# Sheet1.net
KiCad netlist of a schematic drawn in Altium Designer
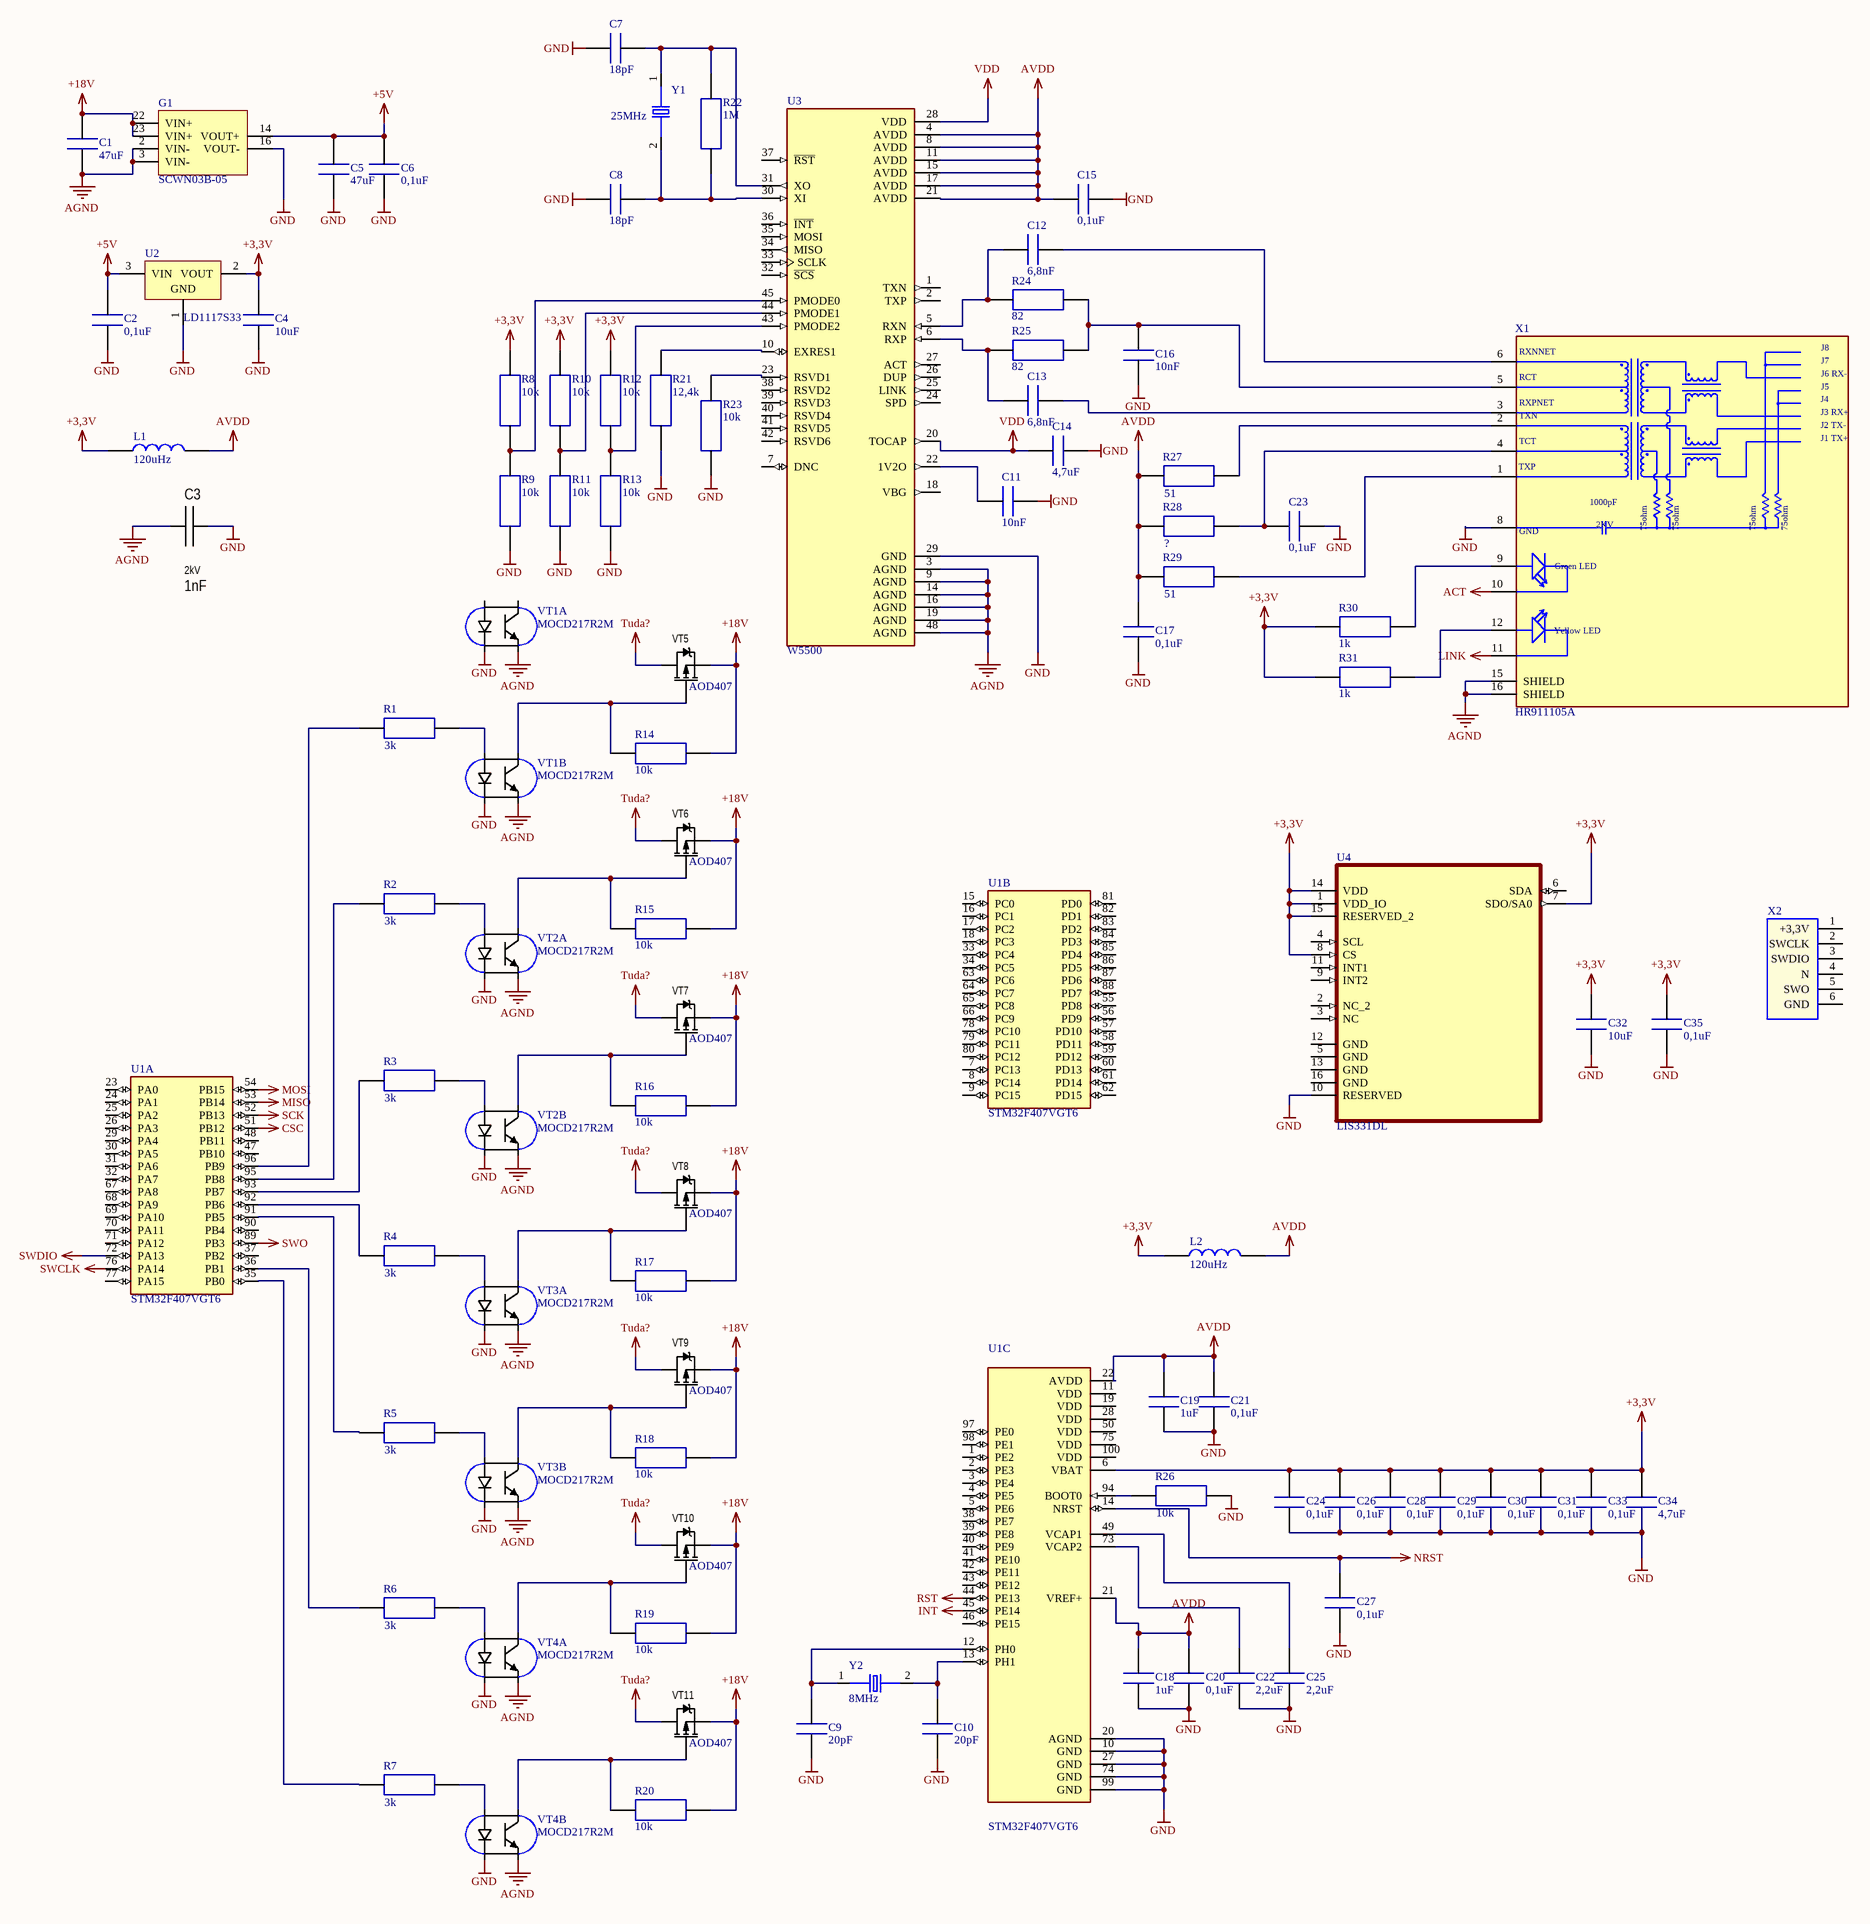
[diagram p0: Sheet1.SchDoc]

(export (version "E")
  (design (tool "Eeschema 10.0.6"))
  (components
    (comp (ref "C1") (value "47uF") (footprint "0603") (libsource (lib "Schlib1") (part "Cap")))
    (comp (ref "C2") (value "0,1uF") (footprint "0603") (libsource (lib "Schlib1") (part "Cap")))
    (comp (ref "C3")
      (value "1nF")
      (footprint "CAP: 1206")
      (fields
        (field (name "MANUFACTURER") "Yageo")
        (field (name "PARTNUMBER") "CC1206KRX7R9BB104")
        (field (name "VALUEMANUFACTURERPARTNUMBER") "Ceramic capacitor, 1nF, X7R, ±10%, 2kV, 1206, -55...+125°C")
        (field (name "VOLTAGE") "2kV")
      )
      (libsource (lib "capacitor") (part "Ceramic_1206"))
    )
    (comp (ref "C4") (value "10uF") (footprint "0603") (libsource (lib "Schlib1") (part "Cap")))
    (comp (ref "C5") (value "47uF") (footprint "0603") (libsource (lib "Schlib1") (part "Cap")))
    (comp (ref "C6") (value "0,1uF") (footprint "0603") (libsource (lib "Schlib1") (part "Cap")))
    (comp (ref "C7") (value "18pF") (footprint "0603") (libsource (lib "Schlib1") (part "Cap")))
    (comp (ref "C8") (value "18pF") (footprint "0603") (libsource (lib "Schlib1") (part "Cap")))
    (comp (ref "C9") (value "20pF") (footprint "0603") (libsource (lib "Schlib1") (part "Cap")))
    (comp (ref "C10") (value "20pF") (footprint "0603") (libsource (lib "Schlib1") (part "Cap")))
    (comp (ref "C11") (value "10nF") (footprint "0603") (libsource (lib "Schlib1") (part "Cap")))
    (comp (ref "C12") (value "6,8nF") (footprint "0603") (libsource (lib "Schlib1") (part "Cap")))
    (comp (ref "C13") (value "6,8nF") (footprint "0603") (libsource (lib "Schlib1") (part "Cap")))
    (comp (ref "C14") (value "4,7uF") (footprint "0603") (libsource (lib "Schlib1") (part "Cap")))
    (comp (ref "C15") (value "0,1uF") (footprint "0603") (libsource (lib "Schlib1") (part "Cap")))
    (comp (ref "C16") (value "10nF") (footprint "0603") (libsource (lib "Schlib1") (part "Cap")))
    (comp (ref "C17") (value "0,1uF") (footprint "0603") (libsource (lib "Schlib1") (part "Cap")))
    (comp (ref "C18") (value "1uF") (footprint "0603") (libsource (lib "Schlib1") (part "Cap")))
    (comp (ref "C19") (value "1uF") (footprint "0603") (libsource (lib "Schlib1") (part "Cap")))
    (comp (ref "C20") (value "0,1uF") (footprint "0603") (libsource (lib "Schlib1") (part "Cap")))
    (comp (ref "C21") (value "0,1uF") (footprint "0603") (libsource (lib "Schlib1") (part "Cap")))
    (comp (ref "C22") (value "2,2uF") (footprint "0603") (libsource (lib "Schlib1") (part "Cap")))
    (comp (ref "C23") (value "0,1uF") (footprint "0603") (libsource (lib "Schlib1") (part "Cap")))
    (comp (ref "C24") (value "0,1uF") (footprint "0603") (libsource (lib "Schlib1") (part "Cap")))
    (comp (ref "C25") (value "2,2uF") (footprint "0603") (libsource (lib "Schlib1") (part "Cap")))
    (comp (ref "C26") (value "0,1uF") (footprint "0603") (libsource (lib "Schlib1") (part "Cap")))
    (comp (ref "C27") (value "0,1uF") (footprint "0603") (libsource (lib "Schlib1") (part "Cap")))
    (comp (ref "C28") (value "0,1uF") (footprint "0603") (libsource (lib "Schlib1") (part "Cap")))
    (comp (ref "C29") (value "0,1uF") (footprint "0603") (libsource (lib "Schlib1") (part "Cap")))
    (comp (ref "C30") (value "0,1uF") (footprint "0603") (libsource (lib "Schlib1") (part "Cap")))
    (comp (ref "C31") (value "0,1uF") (footprint "0603") (libsource (lib "Schlib1") (part "Cap")))
    (comp (ref "C32") (value "10uF") (footprint "0603") (libsource (lib "Schlib1") (part "Cap")))
    (comp (ref "C33") (value "0,1uF") (footprint "0603") (libsource (lib "Schlib1") (part "Cap")))
    (comp (ref "C34") (value "4,7uF") (footprint "0603") (libsource (lib "Schlib1") (part "Cap")))
    (comp (ref "C35") (value "0,1uF") (footprint "0603") (libsource (lib "Schlib1") (part "Cap")))
    (comp (ref "G1")
      (value "SCWN03B-05")
      (footprint "DIP")
      (description "DC-DC Regulated Converter DIP")
      (libsource (lib "Schlib1") (part "SCWN03B-05"))
    )
    (comp (ref "L1") (value "120uHz") (footprint "0603") (libsource (lib "Schlib1") (part "Ind")))
    (comp (ref "L2") (value "120uHz") (footprint "0603") (libsource (lib "Schlib1") (part "Ind")))
    (comp (ref "R1") (value "3k") (footprint "0603") (libsource (lib "Schlib1") (part "Rez")))
    (comp (ref "R2") (value "3k") (footprint "0603") (libsource (lib "Schlib1") (part "Rez")))
    (comp (ref "R3") (value "3k") (footprint "0603") (libsource (lib "Schlib1") (part "Rez")))
    (comp (ref "R4") (value "3k") (footprint "0603") (libsource (lib "Schlib1") (part "Rez")))
    (comp (ref "R5") (value "3k") (footprint "0603") (libsource (lib "Schlib1") (part "Rez")))
    (comp (ref "R6") (value "3k") (footprint "0603") (libsource (lib "Schlib1") (part "Rez")))
    (comp (ref "R7") (value "3k") (footprint "0603") (libsource (lib "Schlib1") (part "Rez")))
    (comp (ref "R8") (value "10k") (footprint "0603") (libsource (lib "Schlib1") (part "Rez")))
    (comp (ref "R9") (value "10k") (footprint "0603") (libsource (lib "Schlib1") (part "Rez")))
    (comp (ref "R10") (value "10k") (footprint "0603") (libsource (lib "Schlib1") (part "Rez")))
    (comp (ref "R11") (value "10k") (footprint "0603") (libsource (lib "Schlib1") (part "Rez")))
    (comp (ref "R12") (value "10k") (footprint "0603") (libsource (lib "Schlib1") (part "Rez")))
    (comp (ref "R13") (value "10k") (footprint "0603") (libsource (lib "Schlib1") (part "Rez")))
    (comp (ref "R14") (value "10k") (footprint "0603") (libsource (lib "Schlib1") (part "Rez")))
    (comp (ref "R15") (value "10k") (footprint "0603") (libsource (lib "Schlib1") (part "Rez")))
    (comp (ref "R16") (value "10k") (footprint "0603") (libsource (lib "Schlib1") (part "Rez")))
    (comp (ref "R17") (value "10k") (footprint "0603") (libsource (lib "Schlib1") (part "Rez")))
    (comp (ref "R18") (value "10k") (footprint "0603") (libsource (lib "Schlib1") (part "Rez")))
    (comp (ref "R19") (value "10k") (footprint "0603") (libsource (lib "Schlib1") (part "Rez")))
    (comp (ref "R20") (value "10k") (footprint "0603") (libsource (lib "Schlib1") (part "Rez")))
    (comp (ref "R21") (value "12,4k") (footprint "0603") (libsource (lib "Schlib1") (part "Rez")))
    (comp (ref "R22") (value "1M") (footprint "0603") (libsource (lib "Schlib1") (part "Rez")))
    (comp (ref "R23") (value "10k") (footprint "0603") (libsource (lib "Schlib1") (part "Rez")))
    (comp (ref "R24") (value "82") (footprint "0603") (libsource (lib "Schlib1") (part "Rez")))
    (comp (ref "R25") (value "82") (footprint "0603") (libsource (lib "Schlib1") (part "Rez")))
    (comp (ref "R26") (value "10k") (footprint "0603") (libsource (lib "Schlib1") (part "Rez")))
    (comp (ref "R27") (value "51") (footprint "0603") (libsource (lib "Schlib1") (part "Rez")))
    (comp (ref "R28") (value "?") (footprint "0603") (libsource (lib "Schlib1") (part "Rez")))
    (comp (ref "R29") (value "51") (footprint "0603") (libsource (lib "Schlib1") (part "Rez")))
    (comp (ref "R30") (value "1k") (footprint "0603") (libsource (lib "Schlib1") (part "Rez")))
    (comp (ref "R31") (value "1k") (footprint "0603") (libsource (lib "Schlib1") (part "Rez")))
    (comp (ref "U1")
      (value "STM32F407VGT6")
      (footprint "QFP50P1600X1600X160-100N")
      (description "ARMÂ® CortexÂ®-M4 STM32F4 Microcontroller IC 32-Bit 168MHz 1MB _1M x 8_ FLASH 100-LQFP _14x14_")
      (fields (field (name "MF") "STMicroelectronics"))
      (libsource (lib "STM32F407VGT6") (part "STM32F407VGT6"))
    )
    (comp (ref "U2")
      (value "LD1117S33")
      (footprint "SOT-223L")
      (description "Adjustable and fixed low drop positive voltage regulator, SOT-223")
      (libsource (lib "Schlib1") (part "LD1117S33"))
    )
    (comp (ref "U3")
      (value "W5500")
      (footprint "QFP50P900X900X160-48N")
      (description "Socket Contact Silver 17-20 AWG Crimp Power")
      (fields (field (name "MF") "WIZnet"))
      (libsource (lib "W5500") (part "W5500"))
    )
    (comp (ref "U4")
      (value "LIS331DL")
      (footprint "LGA16R50P3X5_300X300X100")
      (description "ÐÐºÑÐµÐ»ÐµÑ€Ð¾Ð¼ÐµÑ‚Ñ€ Ð¿Ð¾ Ð¾ÑÑÐ¼ X, Y, Z Â± 2g, 4g, 8g 25 Ð“Ñ† ~ 500 Ð“Ñ† 16-LGA (3x3)")
      (fields (field (name "MF") "STMicroelectronics"))
      (libsource (lib "LIS331DL") (part "LIS331DL"))
    )
    (comp (ref "VT1") (value "MOCD217R2M") (footprint "SO-8") (libsource (lib "Schlib1") (part "Opto")))
    (comp (ref "VT2") (value "MOCD217R2M") (footprint "SO-8") (libsource (lib "Schlib1") (part "Opto")))
    (comp (ref "VT3") (value "MOCD217R2M") (footprint "SO-8") (libsource (lib "Schlib1") (part "Opto")))
    (comp (ref "VT4") (value "MOCD217R2M") (footprint "SO-8") (libsource (lib "Schlib1") (part "Opto")))
    (comp (ref "VT5")
      (value "AOD407")
      (footprint "SOT23")
      (fields
        (field (name "MANUFACTURER") "Infineon Technologies")
        (field (name "VALUEMANUFACTURERPARTNUMBER") "MOSFET P-channel transistor, 20V, 2.6A, 2.9nC, 2.5W, 135mOhm, 220pF, SOT-23, -55...+150°C")
        (field (name "PARTNUMBER") "IRLML2246TRPBF")
      )
      (libsource (lib "transistor") (part "MOSFET_P_123"))
    )
    (comp (ref "VT6")
      (value "AOD407")
      (footprint "SOT23")
      (fields
        (field (name "MANUFACTURER") "Infineon Technologies")
        (field (name "VALUEMANUFACTURERPARTNUMBER") "MOSFET P-channel transistor, 20V, 2.6A, 2.9nC, 2.5W, 135mOhm, 220pF, SOT-23, -55...+150°C")
        (field (name "PARTNUMBER") "IRLML2246TRPBF")
      )
      (libsource (lib "transistor") (part "MOSFET_P_123"))
    )
    (comp (ref "VT7")
      (value "AOD407")
      (footprint "SOT23")
      (fields
        (field (name "MANUFACTURER") "Infineon Technologies")
        (field (name "VALUEMANUFACTURERPARTNUMBER") "MOSFET P-channel transistor, 20V, 2.6A, 2.9nC, 2.5W, 135mOhm, 220pF, SOT-23, -55...+150°C")
        (field (name "PARTNUMBER") "IRLML2246TRPBF")
      )
      (libsource (lib "transistor") (part "MOSFET_P_123"))
    )
    (comp (ref "VT8")
      (value "AOD407")
      (footprint "SOT23")
      (fields
        (field (name "MANUFACTURER") "Infineon Technologies")
        (field (name "VALUEMANUFACTURERPARTNUMBER") "MOSFET P-channel transistor, 20V, 2.6A, 2.9nC, 2.5W, 135mOhm, 220pF, SOT-23, -55...+150°C")
        (field (name "PARTNUMBER") "IRLML2246TRPBF")
      )
      (libsource (lib "transistor") (part "MOSFET_P_123"))
    )
    (comp (ref "VT9")
      (value "AOD407")
      (footprint "SOT23")
      (fields
        (field (name "MANUFACTURER") "Infineon Technologies")
        (field (name "VALUEMANUFACTURERPARTNUMBER") "MOSFET P-channel transistor, 20V, 2.6A, 2.9nC, 2.5W, 135mOhm, 220pF, SOT-23, -55...+150°C")
        (field (name "PARTNUMBER") "IRLML2246TRPBF")
      )
      (libsource (lib "transistor") (part "MOSFET_P_123"))
    )
    (comp (ref "VT10")
      (value "AOD407")
      (footprint "SOT23")
      (fields
        (field (name "MANUFACTURER") "Infineon Technologies")
        (field (name "VALUEMANUFACTURERPARTNUMBER") "MOSFET P-channel transistor, 20V, 2.6A, 2.9nC, 2.5W, 135mOhm, 220pF, SOT-23, -55...+150°C")
        (field (name "PARTNUMBER") "IRLML2246TRPBF")
      )
      (libsource (lib "transistor") (part "MOSFET_P_123"))
    )
    (comp (ref "VT11")
      (value "AOD407")
      (footprint "SOT23")
      (fields
        (field (name "MANUFACTURER") "Infineon Technologies")
        (field (name "VALUEMANUFACTURERPARTNUMBER") "MOSFET P-channel transistor, 20V, 2.6A, 2.9nC, 2.5W, 135mOhm, 220pF, SOT-23, -55...+150°C")
        (field (name "PARTNUMBER") "IRLML2246TRPBF")
      )
      (libsource (lib "transistor") (part "MOSFET_P_123"))
    )
    (comp (ref "X1")
      (value "HR911105A")
      (footprint "HANRUN_HR911105A")
      (description "HR911105A Ethernet Interface Arduino Platform Evaluation Expansion Board")
      (fields (field (name "MF") "DFRobot"))
      (libsource (lib "HR911105A") (part "HR911105A"))
    )
    (comp (ref "X2") (value "PROG") (footprint "3x2x2,54") (libsource (lib "Schlib1") (part "PROG")))
    (comp (ref "Y1")
      (value "25MHz")
      (footprint "XTAL1170X500X450")
      (description "24.576MHz Â±30ppm Crystal 20pF 30 Ohms HC-49/US")
      (fields (field (name "MF") "Fox Electronics") (field (name "MP") "FOXSDLF/245F-20"))
      (libsource (lib "FOXSDLF_245F-20") (part "FOXSDLF/245F-20"))
    )
    (comp (ref "Y2")
      (value "8MHz")
      (footprint "XTAL1170X500X450")
      (description "24.576MHz Â±30ppm Crystal 20pF 30 Ohms HC-49/US")
      (fields (field (name "MF") "Fox Electronics") (field (name "MP") "FOXSDLF/245F-20"))
      (libsource (lib "FOXSDLF_245F-20") (part "FOXSDLF/245F-20"))
    )
  )
  (nets
    (net (code "1") (name "+3,3V") (class "Default")
      (node (ref "C24") (pin "2") (pinfunction "2_2") (pintype "passive"))
      (node (ref "C26") (pin "2") (pinfunction "2_2") (pintype "passive"))
      (node (ref "C28") (pin "2") (pinfunction "2_2") (pintype "passive"))
      (node (ref "C29") (pin "2") (pinfunction "2_2") (pintype "passive"))
      (node (ref "C30") (pin "2") (pinfunction "2_2") (pintype "passive"))
      (node (ref "C31") (pin "2") (pinfunction "2_2") (pintype "passive"))
      (node (ref "C32") (pin "2") (pinfunction "2_2") (pintype "passive"))
      (node (ref "C33") (pin "2") (pinfunction "2_2") (pintype "passive"))
      (node (ref "C34") (pin "2") (pinfunction "2_2") (pintype "passive"))
      (node (ref "C35") (pin "2") (pinfunction "2_2") (pintype "passive"))
      (node (ref "C4") (pin "2") (pinfunction "2_2") (pintype "passive"))
      (node (ref "L1") (pin "1") (pinfunction "1_1") (pintype "passive"))
      (node (ref "L2") (pin "1") (pinfunction "1_1") (pintype "passive"))
      (node (ref "R10") (pin "2") (pinfunction "2_2") (pintype "passive"))
      (node (ref "R12") (pin "2") (pinfunction "2_2") (pintype "passive"))
      (node (ref "R30") (pin "1") (pinfunction "1_1") (pintype "passive"))
      (node (ref "R31") (pin "1") (pinfunction "1_1") (pintype "passive"))
      (node (ref "R8") (pin "2") (pinfunction "2_2") (pintype "passive"))
      (node (ref "U1") (pin "6") (pinfunction "VBAT_6") (pintype "power_in"))
      (node (ref "U2") (pin "2") (pinfunction "VOUT_2") (pintype "power_in"))
      (node (ref "U4") (pin "1") (pinfunction "VDD_IO_1") (pintype "power_in"))
      (node (ref "U4") (pin "14") (pinfunction "VDD_14") (pintype "power_in"))
      (node (ref "U4") (pin "15") (pinfunction "RESERVED_2_15") (pintype "power_in"))
      (node (ref "U4") (pin "7") (pinfunction "SDO/SA0_7") (pintype "output"))
      (node (ref "U4") (pin "8") (pinfunction "CS_8") (pintype "input"))
    )
    (net (code "2") (name "+5V") (class "Default")
      (node (ref "C2") (pin "2") (pinfunction "2_2") (pintype "passive"))
      (node (ref "C5") (pin "2") (pinfunction "2_2") (pintype "passive"))
      (node (ref "C6") (pin "2") (pinfunction "2_2") (pintype "passive"))
      (node (ref "G1") (pin "14") (pinfunction "VOUT+_14") (pintype "power_in"))
      (node (ref "U2") (pin "3") (pinfunction "VIN_3") (pintype "power_in"))
    )
    (net (code "3") (name "+18V") (class "Default")
      (node (ref "C1") (pin "2") (pinfunction "2_2") (pintype "passive"))
      (node (ref "G1") (pin "22") (pinfunction "VIN+_22") (pintype "power_in"))
      (node (ref "G1") (pin "23") (pinfunction "VIN+_23") (pintype "power_in"))
      (node (ref "R14") (pin "2") (pinfunction "2_2") (pintype "passive"))
      (node (ref "R15") (pin "2") (pinfunction "2_2") (pintype "passive"))
      (node (ref "R16") (pin "2") (pinfunction "2_2") (pintype "passive"))
      (node (ref "R17") (pin "2") (pinfunction "2_2") (pintype "passive"))
      (node (ref "R18") (pin "2") (pinfunction "2_2") (pintype "passive"))
      (node (ref "R19") (pin "2") (pinfunction "2_2") (pintype "passive"))
      (node (ref "R20") (pin "2") (pinfunction "2_2") (pintype "passive"))
      (node (ref "VT10") (pin "3") (pinfunction "S_3") (pintype "passive"))
      (node (ref "VT11") (pin "3") (pinfunction "S_3") (pintype "passive"))
      (node (ref "VT5") (pin "3") (pinfunction "S_3") (pintype "passive"))
      (node (ref "VT6") (pin "3") (pinfunction "S_3") (pintype "passive"))
      (node (ref "VT7") (pin "3") (pinfunction "S_3") (pintype "passive"))
      (node (ref "VT8") (pin "3") (pinfunction "S_3") (pintype "passive"))
      (node (ref "VT9") (pin "3") (pinfunction "S_3") (pintype "passive"))
    )
    (net (code "4") (name "ACT") (class "Default")
      (node (ref "X1") (pin "10") (pinfunction "ACT_10") (pintype "passive"))
    )
    (net (code "5") (name "AGND") (class "Default")
      (node (ref "C1") (pin "1") (pinfunction "1_1") (pintype "passive"))
      (node (ref "C3") (pin "1") (pinfunction "1_1") (pintype "passive"))
      (node (ref "G1") (pin "2") (pinfunction "VIN-_2") (pintype "power_in"))
      (node (ref "G1") (pin "3") (pinfunction "VIN-_3") (pintype "power_in"))
      (node (ref "U3") (pin "14") (pinfunction "AGND_14") (pintype "power_in"))
      (node (ref "U3") (pin "16") (pinfunction "AGND_16") (pintype "power_in"))
      (node (ref "U3") (pin "19") (pinfunction "AGND_19") (pintype "power_in"))
      (node (ref "U3") (pin "3") (pinfunction "AGND_3") (pintype "power_in"))
      (node (ref "U3") (pin "48") (pinfunction "AGND_48") (pintype "power_in"))
      (node (ref "U3") (pin "9") (pinfunction "AGND_9") (pintype "power_in"))
      (node (ref "VT1") (pin "5") (pinfunction "E2_5") (pintype "passive"))
      (node (ref "VT1") (pin "7") (pinfunction "E1_7") (pintype "passive"))
      (node (ref "VT2") (pin "5") (pinfunction "E2_5") (pintype "passive"))
      (node (ref "VT2") (pin "7") (pinfunction "E1_7") (pintype "passive"))
      (node (ref "VT3") (pin "5") (pinfunction "E2_5") (pintype "passive"))
      (node (ref "VT3") (pin "7") (pinfunction "E1_7") (pintype "passive"))
      (node (ref "VT4") (pin "5") (pinfunction "E2_5") (pintype "passive"))
      (node (ref "VT4") (pin "7") (pinfunction "E1_7") (pintype "passive"))
      (node (ref "X1") (pin "15") (pinfunction "SHIELD_15") (pintype "passive"))
      (node (ref "X1") (pin "16") (pinfunction "SHIELD_16") (pintype "passive"))
    )
    (net (code "6") (name "AVDD") (class "Default")
      (node (ref "C15") (pin "2") (pinfunction "2_2") (pintype "passive"))
      (node (ref "C17") (pin "1") (pinfunction "1_1") (pintype "passive"))
      (node (ref "C18") (pin "2") (pinfunction "2_2") (pintype "passive"))
      (node (ref "C19") (pin "2") (pinfunction "2_2") (pintype "passive"))
      (node (ref "C20") (pin "2") (pinfunction "2_2") (pintype "passive"))
      (node (ref "C21") (pin "2") (pinfunction "2_2") (pintype "passive"))
      (node (ref "L1") (pin "2") (pinfunction "2_2") (pintype "passive"))
      (node (ref "L2") (pin "2") (pinfunction "2_2") (pintype "passive"))
      (node (ref "R27") (pin "1") (pinfunction "1_1") (pintype "passive"))
      (node (ref "R28") (pin "1") (pinfunction "1_1") (pintype "passive"))
      (node (ref "R29") (pin "1") (pinfunction "1_1") (pintype "passive"))
      (node (ref "U1") (pin "21") (pinfunction "VREF+_21") (pintype "power_in"))
      (node (ref "U1") (pin "22") (pinfunction "AVDD_22") (pintype "power_in"))
      (node (ref "U3") (pin "11") (pinfunction "AVDD_11") (pintype "power_in"))
      (node (ref "U3") (pin "15") (pinfunction "AVDD_15") (pintype "power_in"))
      (node (ref "U3") (pin "17") (pinfunction "AVDD_17") (pintype "power_in"))
      (node (ref "U3") (pin "21") (pinfunction "AVDD_21") (pintype "power_in"))
      (node (ref "U3") (pin "4") (pinfunction "AVDD_4") (pintype "power_in"))
      (node (ref "U3") (pin "8") (pinfunction "AVDD_8") (pintype "power_in"))
    )
    (net (code "7") (name "CSC") (class "Default")
      (node (ref "U1") (pin "51") (pinfunction "PB12_51") (pintype "bidirectional"))
    )
    (net (code "8") (name "GND") (class "Default")
      (node (ref "C10") (pin "1") (pinfunction "1_1") (pintype "passive"))
      (node (ref "C11") (pin "1") (pinfunction "1_1") (pintype "passive"))
      (node (ref "C14") (pin "1") (pinfunction "1_1") (pintype "passive"))
      (node (ref "C15") (pin "1") (pinfunction "1_1") (pintype "passive"))
      (node (ref "C16") (pin "2") (pinfunction "2_2") (pintype "passive"))
      (node (ref "C17") (pin "2") (pinfunction "2_2") (pintype "passive"))
      (node (ref "C18") (pin "1") (pinfunction "1_1") (pintype "passive"))
      (node (ref "C19") (pin "1") (pinfunction "1_1") (pintype "passive"))
      (node (ref "C2") (pin "1") (pinfunction "1_1") (pintype "passive"))
      (node (ref "C20") (pin "1") (pinfunction "1_1") (pintype "passive"))
      (node (ref "C21") (pin "1") (pinfunction "1_1") (pintype "passive"))
      (node (ref "C22") (pin "1") (pinfunction "1_1") (pintype "passive"))
      (node (ref "C23") (pin "2") (pinfunction "2_2") (pintype "passive"))
      (node (ref "C24") (pin "1") (pinfunction "1_1") (pintype "passive"))
      (node (ref "C25") (pin "1") (pinfunction "1_1") (pintype "passive"))
      (node (ref "C26") (pin "1") (pinfunction "1_1") (pintype "passive"))
      (node (ref "C27") (pin "1") (pinfunction "1_1") (pintype "passive"))
      (node (ref "C28") (pin "1") (pinfunction "1_1") (pintype "passive"))
      (node (ref "C29") (pin "1") (pinfunction "1_1") (pintype "passive"))
      (node (ref "C3") (pin "2") (pinfunction "2_2") (pintype "passive"))
      (node (ref "C30") (pin "1") (pinfunction "1_1") (pintype "passive"))
      (node (ref "C31") (pin "1") (pinfunction "1_1") (pintype "passive"))
      (node (ref "C32") (pin "1") (pinfunction "1_1") (pintype "passive"))
      (node (ref "C33") (pin "1") (pinfunction "1_1") (pintype "passive"))
      (node (ref "C34") (pin "1") (pinfunction "1_1") (pintype "passive"))
      (node (ref "C35") (pin "1") (pinfunction "1_1") (pintype "passive"))
      (node (ref "C4") (pin "1") (pinfunction "1_1") (pintype "passive"))
      (node (ref "C5") (pin "1") (pinfunction "1_1") (pintype "passive"))
      (node (ref "C6") (pin "1") (pinfunction "1_1") (pintype "passive"))
      (node (ref "C7") (pin "1") (pinfunction "1_1") (pintype "passive"))
      (node (ref "C8") (pin "1") (pinfunction "1_1") (pintype "passive"))
      (node (ref "C9") (pin "1") (pinfunction "1_1") (pintype "passive"))
      (node (ref "G1") (pin "16") (pinfunction "VOUT-_16") (pintype "passive"))
      (node (ref "R11") (pin "1") (pinfunction "1_1") (pintype "passive"))
      (node (ref "R13") (pin "1") (pinfunction "1_1") (pintype "passive"))
      (node (ref "R21") (pin "1") (pinfunction "1_1") (pintype "passive"))
      (node (ref "R23") (pin "1") (pinfunction "1_1") (pintype "passive"))
      (node (ref "R26") (pin "2") (pinfunction "2_2") (pintype "passive"))
      (node (ref "R9") (pin "1") (pinfunction "1_1") (pintype "passive"))
      (node (ref "U1") (pin "10") (pinfunction "GND_10") (pintype "power_in"))
      (node (ref "U1") (pin "20") (pinfunction "AGND_20") (pintype "power_in"))
      (node (ref "U1") (pin "27") (pinfunction "GND_27") (pintype "power_in"))
      (node (ref "U1") (pin "74") (pinfunction "GND_74") (pintype "power_in"))
      (node (ref "U1") (pin "99") (pinfunction "GND_99") (pintype "power_in"))
      (node (ref "U2") (pin "1") (pinfunction "GND_1") (pintype "power_in"))
      (node (ref "U3") (pin "29") (pinfunction "GND_29") (pintype "passive"))
      (node (ref "U4") (pin "10") (pinfunction "RESERVED_10") (pintype "passive"))
      (node (ref "VT1") (pin "2") (pinfunction "Ca1_2") (pintype "passive"))
      (node (ref "VT1") (pin "4") (pinfunction "Ca2_4") (pintype "passive"))
      (node (ref "VT2") (pin "2") (pinfunction "Ca1_2") (pintype "passive"))
      (node (ref "VT2") (pin "4") (pinfunction "Ca2_4") (pintype "passive"))
      (node (ref "VT3") (pin "2") (pinfunction "Ca1_2") (pintype "passive"))
      (node (ref "VT3") (pin "4") (pinfunction "Ca2_4") (pintype "passive"))
      (node (ref "VT4") (pin "2") (pinfunction "Ca1_2") (pintype "passive"))
      (node (ref "VT4") (pin "4") (pinfunction "Ca2_4") (pintype "passive"))
      (node (ref "X1") (pin "8") (pinfunction "GND_8") (pintype "power_in"))
    )
    (net (code "9") (name "INT") (class "Default")
      (node (ref "U1") (pin "45") (pinfunction "PE14_45") (pintype "bidirectional"))
    )
    (net (code "10") (name "LINK") (class "Default")
      (node (ref "X1") (pin "11") (pinfunction "LINK_11") (pintype "passive"))
    )
    (net (code "11") (name "MISO") (class "Default")
      (node (ref "U1") (pin "53") (pinfunction "PB14_53") (pintype "bidirectional"))
    )
    (net (code "12") (name "MOSI") (class "Default")
      (node (ref "U1") (pin "54") (pinfunction "PB15_54") (pintype "bidirectional"))
    )
    (net (code "13") (name "NRST") (class "Default")
      (node (ref "C27") (pin "2") (pinfunction "2_2") (pintype "passive"))
      (node (ref "U1") (pin "14") (pinfunction "NRST_14") (pintype "bidirectional"))
    )
    (net (code "14") (name "Net-(U1A-PB0)") (class "Default")
      (node (ref "R7") (pin "1") (pinfunction "1_1") (pintype "passive"))
      (node (ref "U1") (pin "35") (pinfunction "PB0_35") (pintype "bidirectional"))
    )
    (net (code "15") (name "Net-(U1A-PB1)") (class "Default")
      (node (ref "R6") (pin "1") (pinfunction "1_1") (pintype "passive"))
      (node (ref "U1") (pin "36") (pinfunction "PB1_36") (pintype "bidirectional"))
    )
    (net (code "16") (name "Net-(U1A-PB5)") (class "Default")
      (node (ref "R5") (pin "1") (pinfunction "1_1") (pintype "passive"))
      (node (ref "U1") (pin "91") (pinfunction "PB5_91") (pintype "bidirectional"))
    )
    (net (code "17") (name "Net-(U1A-PB6)") (class "Default")
      (node (ref "R4") (pin "1") (pinfunction "1_1") (pintype "passive"))
      (node (ref "U1") (pin "92") (pinfunction "PB6_92") (pintype "bidirectional"))
    )
    (net (code "18") (name "Net-(U1A-PB7)") (class "Default")
      (node (ref "R3") (pin "1") (pinfunction "1_1") (pintype "passive"))
      (node (ref "U1") (pin "93") (pinfunction "PB7_93") (pintype "bidirectional"))
    )
    (net (code "19") (name "Net-(U1A-PB8)") (class "Default")
      (node (ref "R2") (pin "1") (pinfunction "1_1") (pintype "passive"))
      (node (ref "U1") (pin "95") (pinfunction "PB8_95") (pintype "bidirectional"))
    )
    (net (code "20") (name "Net-(U1A-PB9)") (class "Default")
      (node (ref "R1") (pin "1") (pinfunction "1_1") (pintype "passive"))
      (node (ref "U1") (pin "96") (pinfunction "PB9_96") (pintype "bidirectional"))
    )
    (net (code "21") (name "Net-(U1C-BOOT0)") (class "Default")
      (node (ref "R26") (pin "1") (pinfunction "1_1") (pintype "passive"))
      (node (ref "U1") (pin "94") (pinfunction "BOOT0_94") (pintype "input"))
    )
    (net (code "22") (name "Net-(U1C-PH0)") (class "Default")
      (node (ref "C9") (pin "2") (pinfunction "2_2") (pintype "passive"))
      (node (ref "U1") (pin "12") (pinfunction "PH0_12") (pintype "bidirectional"))
      (node (ref "Y2") (pin "1") (pintype "passive"))
    )
    (net (code "23") (name "Net-(U1C-PH1)") (class "Default")
      (node (ref "C10") (pin "2") (pinfunction "2_2") (pintype "passive"))
      (node (ref "U1") (pin "13") (pinfunction "PH1_13") (pintype "bidirectional"))
      (node (ref "Y2") (pin "2") (pintype "passive"))
    )
    (net (code "24") (name "Net-(U1C-VCAP1)") (class "Default")
      (node (ref "C25") (pin "2") (pinfunction "2_2") (pintype "passive"))
      (node (ref "U1") (pin "49") (pinfunction "VCAP1_49") (pintype "passive"))
    )
    (net (code "25") (name "Net-(U1C-VCAP2)") (class "Default")
      (node (ref "C22") (pin "2") (pinfunction "2_2") (pintype "passive"))
      (node (ref "U1") (pin "73") (pinfunction "VCAP2_73") (pintype "passive"))
    )
    (net (code "26") (name "Net-(U3-1V2O)") (class "Default")
      (node (ref "C11") (pin "2") (pinfunction "2_2") (pintype "passive"))
      (node (ref "U3") (pin "22") (pinfunction "1V2O_22") (pintype "output"))
    )
    (net (code "27") (name "Net-(U3-EXRES1)") (class "Default")
      (node (ref "R21") (pin "2") (pinfunction "2_2") (pintype "passive"))
      (node (ref "U3") (pin "10") (pinfunction "EXRES1_10") (pintype "bidirectional"))
    )
    (net (code "28") (name "Net-(U3-PMODE0)") (class "Default")
      (node (ref "R8") (pin "1") (pinfunction "1_1") (pintype "passive"))
      (node (ref "R9") (pin "2") (pinfunction "2_2") (pintype "passive"))
      (node (ref "U3") (pin "45") (pinfunction "PMODE0_45") (pintype "input"))
    )
    (net (code "29") (name "Net-(U3-PMODE1)") (class "Default")
      (node (ref "R10") (pin "1") (pinfunction "1_1") (pintype "passive"))
      (node (ref "R11") (pin "2") (pinfunction "2_2") (pintype "passive"))
      (node (ref "U3") (pin "44") (pinfunction "PMODE1_44") (pintype "input"))
    )
    (net (code "30") (name "Net-(U3-PMODE2)") (class "Default")
      (node (ref "R12") (pin "1") (pinfunction "1_1") (pintype "passive"))
      (node (ref "R13") (pin "2") (pinfunction "2_2") (pintype "passive"))
      (node (ref "U3") (pin "43") (pinfunction "PMODE2_43") (pintype "input"))
    )
    (net (code "31") (name "Net-(U3-RSVD1)") (class "Default")
      (node (ref "R23") (pin "2") (pinfunction "2_2") (pintype "passive"))
      (node (ref "U3") (pin "23") (pinfunction "RSVD1_23") (pintype "input"))
    )
    (net (code "32") (name "Net-(U3-RXN)") (class "Default")
      (node (ref "C12") (pin "2") (pinfunction "2_2") (pintype "passive"))
      (node (ref "R24") (pin "1") (pinfunction "1_1") (pintype "passive"))
      (node (ref "U3") (pin "5") (pinfunction "RXN_5") (pintype "input"))
    )
    (net (code "33") (name "Net-(U3-RXP)") (class "Default")
      (node (ref "C13") (pin "2") (pinfunction "2_2") (pintype "passive"))
      (node (ref "R25") (pin "1") (pinfunction "1_1") (pintype "passive"))
      (node (ref "U3") (pin "6") (pinfunction "RXP_6") (pintype "input"))
    )
    (net (code "34") (name "Net-(U3-XI)") (class "Default")
      (node (ref "C8") (pin "2") (pinfunction "2_2") (pintype "passive"))
      (node (ref "R22") (pin "2") (pinfunction "2_2") (pintype "passive"))
      (node (ref "U3") (pin "30") (pinfunction "XI_30") (pintype "input"))
      (node (ref "Y1") (pin "2") (pintype "passive"))
    )
    (net (code "35") (name "Net-(U3-XO)") (class "Default")
      (node (ref "C7") (pin "2") (pinfunction "2_2") (pintype "passive"))
      (node (ref "R22") (pin "1") (pinfunction "1_1") (pintype "passive"))
      (node (ref "U3") (pin "31") (pinfunction "XO_31") (pintype "output"))
      (node (ref "Y1") (pin "1") (pintype "passive"))
    )
    (net (code "36") (name "Net-(VT1B-A2)") (class "Default")
      (node (ref "R1") (pin "2") (pinfunction "2_2") (pintype "passive"))
      (node (ref "VT1") (pin "3") (pinfunction "A2_3") (pintype "passive"))
    )
    (net (code "37") (name "Net-(VT1B-C2)") (class "Default")
      (node (ref "R14") (pin "1") (pinfunction "1_1") (pintype "passive"))
      (node (ref "VT1") (pin "6") (pinfunction "C2_6") (pintype "passive"))
      (node (ref "VT5") (pin "1") (pinfunction "G_1") (pintype "passive"))
    )
    (net (code "38") (name "Net-(VT2A-A1)") (class "Default")
      (node (ref "R2") (pin "2") (pinfunction "2_2") (pintype "passive"))
      (node (ref "VT2") (pin "1") (pinfunction "A1_1") (pintype "passive"))
    )
    (net (code "39") (name "Net-(VT2A-C1)") (class "Default")
      (node (ref "R15") (pin "1") (pinfunction "1_1") (pintype "passive"))
      (node (ref "VT2") (pin "8") (pinfunction "C1_8") (pintype "passive"))
      (node (ref "VT6") (pin "1") (pinfunction "G_1") (pintype "passive"))
    )
    (net (code "40") (name "Net-(VT2B-A2)") (class "Default")
      (node (ref "R3") (pin "2") (pinfunction "2_2") (pintype "passive"))
      (node (ref "VT2") (pin "3") (pinfunction "A2_3") (pintype "passive"))
    )
    (net (code "41") (name "Net-(VT2B-C2)") (class "Default")
      (node (ref "R16") (pin "1") (pinfunction "1_1") (pintype "passive"))
      (node (ref "VT2") (pin "6") (pinfunction "C2_6") (pintype "passive"))
      (node (ref "VT7") (pin "1") (pinfunction "G_1") (pintype "passive"))
    )
    (net (code "42") (name "Net-(VT3A-A1)") (class "Default")
      (node (ref "R4") (pin "2") (pinfunction "2_2") (pintype "passive"))
      (node (ref "VT3") (pin "1") (pinfunction "A1_1") (pintype "passive"))
    )
    (net (code "43") (name "Net-(VT3A-C1)") (class "Default")
      (node (ref "R17") (pin "1") (pinfunction "1_1") (pintype "passive"))
      (node (ref "VT3") (pin "8") (pinfunction "C1_8") (pintype "passive"))
      (node (ref "VT8") (pin "1") (pinfunction "G_1") (pintype "passive"))
    )
    (net (code "44") (name "Net-(VT3B-A2)") (class "Default")
      (node (ref "R5") (pin "2") (pinfunction "2_2") (pintype "passive"))
      (node (ref "VT3") (pin "3") (pinfunction "A2_3") (pintype "passive"))
    )
    (net (code "45") (name "Net-(VT3B-C2)") (class "Default")
      (node (ref "R18") (pin "1") (pinfunction "1_1") (pintype "passive"))
      (node (ref "VT3") (pin "6") (pinfunction "C2_6") (pintype "passive"))
      (node (ref "VT9") (pin "1") (pinfunction "G_1") (pintype "passive"))
    )
    (net (code "46") (name "Net-(VT4A-A1)") (class "Default")
      (node (ref "R6") (pin "2") (pinfunction "2_2") (pintype "passive"))
      (node (ref "VT4") (pin "1") (pinfunction "A1_1") (pintype "passive"))
    )
    (net (code "47") (name "Net-(VT4B-A2)") (class "Default")
      (node (ref "R7") (pin "2") (pinfunction "2_2") (pintype "passive"))
      (node (ref "VT4") (pin "3") (pinfunction "A2_3") (pintype "passive"))
    )
    (net (code "48") (name "Net-(VT10-G)") (class "Default")
      (node (ref "R19") (pin "1") (pinfunction "1_1") (pintype "passive"))
      (node (ref "VT10") (pin "1") (pinfunction "G_1") (pintype "passive"))
      (node (ref "VT4") (pin "8") (pinfunction "C1_8") (pintype "passive"))
    )
    (net (code "49") (name "Net-(VT11-G)") (class "Default")
      (node (ref "R20") (pin "1") (pinfunction "1_1") (pintype "passive"))
      (node (ref "VT11") (pin "1") (pinfunction "G_1") (pintype "passive"))
      (node (ref "VT4") (pin "6") (pinfunction "C2_6") (pintype "passive"))
    )
    (net (code "50") (name "Net-(X1-GA)") (class "Default")
      (node (ref "R30") (pin "2") (pinfunction "2_2") (pintype "passive"))
      (node (ref "X1") (pin "9") (pinfunction "GA_9") (pintype "passive"))
    )
    (net (code "51") (name "Net-(X1-RCT)") (class "Default")
      (node (ref "C16") (pin "1") (pinfunction "1_1") (pintype "passive"))
      (node (ref "R24") (pin "2") (pinfunction "2_2") (pintype "passive"))
      (node (ref "R25") (pin "2") (pinfunction "2_2") (pintype "passive"))
      (node (ref "X1") (pin "5") (pinfunction "RCT_5") (pintype "passive"))
    )
    (net (code "52") (name "Net-(X1-RXNNET)") (class "Default")
      (node (ref "C12") (pin "1") (pinfunction "1_1") (pintype "passive"))
      (node (ref "X1") (pin "6") (pinfunction "RXNNET_6") (pintype "passive"))
    )
    (net (code "53") (name "Net-(X1-RXPNET)") (class "Default")
      (node (ref "C13") (pin "1") (pinfunction "1_1") (pintype "passive"))
      (node (ref "X1") (pin "3") (pinfunction "RXPNET_3") (pintype "passive"))
    )
    (net (code "54") (name "Net-(X1-TCT)") (class "Default")
      (node (ref "C23") (pin "1") (pinfunction "1_1") (pintype "passive"))
      (node (ref "R28") (pin "2") (pinfunction "2_2") (pintype "passive"))
      (node (ref "X1") (pin "4") (pinfunction "TCT_4") (pintype "passive"))
    )
    (net (code "55") (name "Net-(X1-TXN)") (class "Default")
      (node (ref "R27") (pin "2") (pinfunction "2_2") (pintype "passive"))
      (node (ref "X1") (pin "2") (pinfunction "TXN_2") (pintype "passive"))
    )
    (net (code "56") (name "Net-(X1-TXP)") (class "Default")
      (node (ref "R29") (pin "2") (pinfunction "2_2") (pintype "passive"))
      (node (ref "X1") (pin "1") (pinfunction "TXP_1") (pintype "passive"))
    )
    (net (code "57") (name "Net-(X1-YA)") (class "Default")
      (node (ref "R31") (pin "2") (pinfunction "2_2") (pintype "passive"))
      (node (ref "X1") (pin "12") (pinfunction "YA_12") (pintype "passive"))
    )
    (net (code "58") (name "RST") (class "Default")
      (node (ref "U1") (pin "44") (pinfunction "PE13_44") (pintype "bidirectional"))
    )
    (net (code "59") (name "SCK") (class "Default")
      (node (ref "U1") (pin "52") (pinfunction "PB13_52") (pintype "bidirectional"))
    )
    (net (code "60") (name "SWCLK") (class "Default")
      (node (ref "U1") (pin "76") (pinfunction "PA14_76") (pintype "bidirectional"))
    )
    (net (code "61") (name "SWDIO") (class "Default")
      (node (ref "U1") (pin "72") (pinfunction "PA13_72") (pintype "bidirectional"))
    )
    (net (code "62") (name "SWO") (class "Default")
      (node (ref "U1") (pin "89") (pinfunction "PB3_89") (pintype "bidirectional"))
    )
    (net (code "63") (name "Tuda?") (class "Default")
      (node (ref "VT10") (pin "2") (pinfunction "D_2") (pintype "passive"))
      (node (ref "VT11") (pin "2") (pinfunction "D_2") (pintype "passive"))
      (node (ref "VT5") (pin "2") (pinfunction "D_2") (pintype "passive"))
      (node (ref "VT6") (pin "2") (pinfunction "D_2") (pintype "passive"))
      (node (ref "VT7") (pin "2") (pinfunction "D_2") (pintype "passive"))
      (node (ref "VT8") (pin "2") (pinfunction "D_2") (pintype "passive"))
      (node (ref "VT9") (pin "2") (pinfunction "D_2") (pintype "passive"))
    )
    (net (code "64") (name "VDD") (class "Default")
      (node (ref "C14") (pin "2") (pinfunction "2_2") (pintype "passive"))
      (node (ref "U3") (pin "20") (pinfunction "TOCAP_20") (pintype "output"))
      (node (ref "U3") (pin "28") (pinfunction "VDD_28") (pintype "power_in"))
    )
    (net (code "65") (name "unconnected-(U1A-PA0-Pad23)") (class "Default")
      (node (ref "U1") (pin "23") (pinfunction "PA0_23") (pintype "bidirectional"))
    )
    (net (code "66") (name "unconnected-(U1A-PA1-Pad24)") (class "Default")
      (node (ref "U1") (pin "24") (pinfunction "PA1_24") (pintype "bidirectional"))
    )
    (net (code "67") (name "unconnected-(U1A-PA2-Pad25)") (class "Default")
      (node (ref "U1") (pin "25") (pinfunction "PA2_25") (pintype "bidirectional"))
    )
    (net (code "68") (name "unconnected-(U1A-PA3-Pad26)") (class "Default")
      (node (ref "U1") (pin "26") (pinfunction "PA3_26") (pintype "bidirectional"))
    )
    (net (code "69") (name "unconnected-(U1A-PA4-Pad29)") (class "Default")
      (node (ref "U1") (pin "29") (pinfunction "PA4_29") (pintype "bidirectional"))
    )
    (net (code "70") (name "unconnected-(U1A-PA5-Pad30)") (class "Default")
      (node (ref "U1") (pin "30") (pinfunction "PA5_30") (pintype "bidirectional"))
    )
    (net (code "71") (name "unconnected-(U1A-PA6-Pad31)") (class "Default")
      (node (ref "U1") (pin "31") (pinfunction "PA6_31") (pintype "bidirectional"))
    )
    (net (code "72") (name "unconnected-(U1A-PA7-Pad32)") (class "Default")
      (node (ref "U1") (pin "32") (pinfunction "PA7_32") (pintype "bidirectional"))
    )
    (net (code "73") (name "unconnected-(U1A-PA8-Pad67)") (class "Default")
      (node (ref "U1") (pin "67") (pinfunction "PA8_67") (pintype "bidirectional"))
    )
    (net (code "74") (name "unconnected-(U1A-PA9-Pad68)") (class "Default")
      (node (ref "U1") (pin "68") (pinfunction "PA9_68") (pintype "bidirectional"))
    )
    (net (code "75") (name "unconnected-(U1A-PA10-Pad69)") (class "Default")
      (node (ref "U1") (pin "69") (pinfunction "PA10_69") (pintype "bidirectional"))
    )
    (net (code "76") (name "unconnected-(U1A-PA11-Pad70)") (class "Default")
      (node (ref "U1") (pin "70") (pinfunction "PA11_70") (pintype "bidirectional"))
    )
    (net (code "77") (name "unconnected-(U1A-PA12-Pad71)") (class "Default")
      (node (ref "U1") (pin "71") (pinfunction "PA12_71") (pintype "bidirectional"))
    )
    (net (code "78") (name "unconnected-(U1A-PA15-Pad77)") (class "Default")
      (node (ref "U1") (pin "77") (pinfunction "PA15_77") (pintype "bidirectional"))
    )
    (net (code "79") (name "unconnected-(U1A-PB2-Pad37)") (class "Default")
      (node (ref "U1") (pin "37") (pinfunction "PB2_37") (pintype "bidirectional"))
    )
    (net (code "80") (name "unconnected-(U1A-PB4-Pad90)") (class "Default")
      (node (ref "U1") (pin "90") (pinfunction "PB4_90") (pintype "bidirectional"))
    )
    (net (code "81") (name "unconnected-(U1A-PB10-Pad47)") (class "Default")
      (node (ref "U1") (pin "47") (pinfunction "PB10_47") (pintype "bidirectional"))
    )
    (net (code "82") (name "unconnected-(U1A-PB11-Pad48)") (class "Default")
      (node (ref "U1") (pin "48") (pinfunction "PB11_48") (pintype "bidirectional"))
    )
    (net (code "83") (name "unconnected-(U1B-PC0-Pad15)") (class "Default")
      (node (ref "U1") (pin "15") (pinfunction "PC0_15") (pintype "bidirectional"))
    )
    (net (code "84") (name "unconnected-(U1B-PC1-Pad16)") (class "Default")
      (node (ref "U1") (pin "16") (pinfunction "PC1_16") (pintype "bidirectional"))
    )
    (net (code "85") (name "unconnected-(U1B-PC2-Pad17)") (class "Default")
      (node (ref "U1") (pin "17") (pinfunction "PC2_17") (pintype "bidirectional"))
    )
    (net (code "86") (name "unconnected-(U1B-PC3-Pad18)") (class "Default")
      (node (ref "U1") (pin "18") (pinfunction "PC3_18") (pintype "bidirectional"))
    )
    (net (code "87") (name "unconnected-(U1B-PC4-Pad33)") (class "Default")
      (node (ref "U1") (pin "33") (pinfunction "PC4_33") (pintype "bidirectional"))
    )
    (net (code "88") (name "unconnected-(U1B-PC5-Pad34)") (class "Default")
      (node (ref "U1") (pin "34") (pinfunction "PC5_34") (pintype "bidirectional"))
    )
    (net (code "89") (name "unconnected-(U1B-PC6-Pad63)") (class "Default")
      (node (ref "U1") (pin "63") (pinfunction "PC6_63") (pintype "bidirectional"))
    )
    (net (code "90") (name "unconnected-(U1B-PC7-Pad64)") (class "Default")
      (node (ref "U1") (pin "64") (pinfunction "PC7_64") (pintype "bidirectional"))
    )
    (net (code "91") (name "unconnected-(U1B-PC8-Pad65)") (class "Default")
      (node (ref "U1") (pin "65") (pinfunction "PC8_65") (pintype "bidirectional"))
    )
    (net (code "92") (name "unconnected-(U1B-PC9-Pad66)") (class "Default")
      (node (ref "U1") (pin "66") (pinfunction "PC9_66") (pintype "bidirectional"))
    )
    (net (code "93") (name "unconnected-(U1B-PC10-Pad78)") (class "Default")
      (node (ref "U1") (pin "78") (pinfunction "PC10_78") (pintype "bidirectional"))
    )
    (net (code "94") (name "unconnected-(U1B-PC11-Pad79)") (class "Default")
      (node (ref "U1") (pin "79") (pinfunction "PC11_79") (pintype "bidirectional"))
    )
    (net (code "95") (name "unconnected-(U1B-PC12-Pad80)") (class "Default")
      (node (ref "U1") (pin "80") (pinfunction "PC12_80") (pintype "bidirectional"))
    )
    (net (code "96") (name "unconnected-(U1B-PC13-Pad7)") (class "Default")
      (node (ref "U1") (pin "7") (pinfunction "PC13_7") (pintype "bidirectional"))
    )
    (net (code "97") (name "unconnected-(U1B-PC14-Pad8)") (class "Default")
      (node (ref "U1") (pin "8") (pinfunction "PC14_8") (pintype "bidirectional"))
    )
    (net (code "98") (name "unconnected-(U1B-PC15-Pad9)") (class "Default")
      (node (ref "U1") (pin "9") (pinfunction "PC15_9") (pintype "bidirectional"))
    )
    (net (code "99") (name "unconnected-(U1B-PD0-Pad81)") (class "Default")
      (node (ref "U1") (pin "81") (pinfunction "PD0_81") (pintype "bidirectional"))
    )
    (net (code "100") (name "unconnected-(U1B-PD1-Pad82)") (class "Default")
      (node (ref "U1") (pin "82") (pinfunction "PD1_82") (pintype "bidirectional"))
    )
    (net (code "101") (name "unconnected-(U1B-PD2-Pad83)") (class "Default")
      (node (ref "U1") (pin "83") (pinfunction "PD2_83") (pintype "bidirectional"))
    )
    (net (code "102") (name "unconnected-(U1B-PD3-Pad84)") (class "Default")
      (node (ref "U1") (pin "84") (pinfunction "PD3_84") (pintype "bidirectional"))
    )
    (net (code "103") (name "unconnected-(U1B-PD4-Pad85)") (class "Default")
      (node (ref "U1") (pin "85") (pinfunction "PD4_85") (pintype "bidirectional"))
    )
    (net (code "104") (name "unconnected-(U1B-PD5-Pad86)") (class "Default")
      (node (ref "U1") (pin "86") (pinfunction "PD5_86") (pintype "bidirectional"))
    )
    (net (code "105") (name "unconnected-(U1B-PD6-Pad87)") (class "Default")
      (node (ref "U1") (pin "87") (pinfunction "PD6_87") (pintype "bidirectional"))
    )
    (net (code "106") (name "unconnected-(U1B-PD7-Pad88)") (class "Default")
      (node (ref "U1") (pin "88") (pinfunction "PD7_88") (pintype "bidirectional"))
    )
    (net (code "107") (name "unconnected-(U1B-PD8-Pad55)") (class "Default")
      (node (ref "U1") (pin "55") (pinfunction "PD8_55") (pintype "bidirectional"))
    )
    (net (code "108") (name "unconnected-(U1B-PD9-Pad56)") (class "Default")
      (node (ref "U1") (pin "56") (pinfunction "PD9_56") (pintype "bidirectional"))
    )
    (net (code "109") (name "unconnected-(U1B-PD10-Pad57)") (class "Default")
      (node (ref "U1") (pin "57") (pinfunction "PD10_57") (pintype "bidirectional"))
    )
    (net (code "110") (name "unconnected-(U1B-PD11-Pad58)") (class "Default")
      (node (ref "U1") (pin "58") (pinfunction "PD11_58") (pintype "bidirectional"))
    )
    (net (code "111") (name "unconnected-(U1B-PD12-Pad59)") (class "Default")
      (node (ref "U1") (pin "59") (pinfunction "PD12_59") (pintype "bidirectional"))
    )
    (net (code "112") (name "unconnected-(U1B-PD13-Pad60)") (class "Default")
      (node (ref "U1") (pin "60") (pinfunction "PD13_60") (pintype "bidirectional"))
    )
    (net (code "113") (name "unconnected-(U1B-PD14-Pad61)") (class "Default")
      (node (ref "U1") (pin "61") (pinfunction "PD14_61") (pintype "bidirectional"))
    )
    (net (code "114") (name "unconnected-(U1B-PD15-Pad62)") (class "Default")
      (node (ref "U1") (pin "62") (pinfunction "PD15_62") (pintype "bidirectional"))
    )
    (net (code "115") (name "unconnected-(U1C-PE0-Pad97)") (class "Default")
      (node (ref "U1") (pin "97") (pinfunction "PE0_97") (pintype "bidirectional"))
    )
    (net (code "116") (name "unconnected-(U1C-PE1-Pad98)") (class "Default")
      (node (ref "U1") (pin "98") (pinfunction "PE1_98") (pintype "bidirectional"))
    )
    (net (code "117") (name "unconnected-(U1C-PE2-Pad1)") (class "Default")
      (node (ref "U1") (pin "1") (pinfunction "PE2_1") (pintype "bidirectional"))
    )
    (net (code "118") (name "unconnected-(U1C-PE3-Pad2)") (class "Default")
      (node (ref "U1") (pin "2") (pinfunction "PE3_2") (pintype "bidirectional"))
    )
    (net (code "119") (name "unconnected-(U1C-PE4-Pad3)") (class "Default")
      (node (ref "U1") (pin "3") (pinfunction "PE4_3") (pintype "bidirectional"))
    )
    (net (code "120") (name "unconnected-(U1C-PE5-Pad4)") (class "Default")
      (node (ref "U1") (pin "4") (pinfunction "PE5_4") (pintype "bidirectional"))
    )
    (net (code "121") (name "unconnected-(U1C-PE6-Pad5)") (class "Default")
      (node (ref "U1") (pin "5") (pinfunction "PE6_5") (pintype "bidirectional"))
    )
    (net (code "122") (name "unconnected-(U1C-PE7-Pad38)") (class "Default")
      (node (ref "U1") (pin "38") (pinfunction "PE7_38") (pintype "bidirectional"))
    )
    (net (code "123") (name "unconnected-(U1C-PE8-Pad39)") (class "Default")
      (node (ref "U1") (pin "39") (pinfunction "PE8_39") (pintype "bidirectional"))
    )
    (net (code "124") (name "unconnected-(U1C-PE9-Pad40)") (class "Default")
      (node (ref "U1") (pin "40") (pinfunction "PE9_40") (pintype "bidirectional"))
    )
    (net (code "125") (name "unconnected-(U1C-PE10-Pad41)") (class "Default")
      (node (ref "U1") (pin "41") (pinfunction "PE10_41") (pintype "bidirectional"))
    )
    (net (code "126") (name "unconnected-(U1C-PE11-Pad42)") (class "Default")
      (node (ref "U1") (pin "42") (pinfunction "PE11_42") (pintype "bidirectional"))
    )
    (net (code "127") (name "unconnected-(U1C-PE12-Pad43)") (class "Default")
      (node (ref "U1") (pin "43") (pinfunction "PE12_43") (pintype "bidirectional"))
    )
    (net (code "128") (name "unconnected-(U1C-PE15-Pad46)") (class "Default")
      (node (ref "U1") (pin "46") (pinfunction "PE15_46") (pintype "bidirectional"))
    )
    (net (code "129") (name "unconnected-(U1C-VDD-Pad11)") (class "Default")
      (node (ref "U1") (pin "11") (pinfunction "VDD_11") (pintype "power_in"))
    )
    (net (code "130") (name "unconnected-(U1C-VDD-Pad19)") (class "Default")
      (node (ref "U1") (pin "19") (pinfunction "VDD_19") (pintype "power_in"))
    )
    (net (code "131") (name "unconnected-(U1C-VDD-Pad28)") (class "Default")
      (node (ref "U1") (pin "28") (pinfunction "VDD_28") (pintype "power_in"))
    )
    (net (code "132") (name "unconnected-(U1C-VDD-Pad50)") (class "Default")
      (node (ref "U1") (pin "50") (pinfunction "VDD_50") (pintype "power_in"))
    )
    (net (code "133") (name "unconnected-(U1C-VDD-Pad75)") (class "Default")
      (node (ref "U1") (pin "75") (pinfunction "VDD_75") (pintype "power_in"))
    )
    (net (code "134") (name "unconnected-(U1C-VDD-Pad100)") (class "Default")
      (node (ref "U1") (pin "100") (pinfunction "VDD_100") (pintype "power_in"))
    )
    (net (code "135") (name "unconnected-(U3-ACT-Pad27)") (class "Default")
      (node (ref "U3") (pin "27") (pinfunction "ACT_27") (pintype "output"))
    )
    (net (code "136") (name "unconnected-(U3-DNC-Pad7)") (class "Default")
      (node (ref "U3") (pin "7") (pinfunction "DNC_7") (pintype "bidirectional"))
    )
    (net (code "137") (name "unconnected-(U3-DUP-Pad26)") (class "Default")
      (node (ref "U3") (pin "26") (pinfunction "DUP_26") (pintype "output"))
    )
    (net (code "138") (name "unconnected-(U3-LINK-Pad25)") (class "Default")
      (node (ref "U3") (pin "25") (pinfunction "LINK_25") (pintype "output"))
    )
    (net (code "139") (name "unconnected-(U3-MISO-Pad34)") (class "Default")
      (node (ref "U3") (pin "34") (pinfunction "MISO_34") (pintype "output"))
    )
    (net (code "140") (name "unconnected-(U3-MOSI-Pad35)") (class "Default")
      (node (ref "U3") (pin "35") (pinfunction "MOSI_35") (pintype "input"))
    )
    (net (code "141") (name "unconnected-(U3-RSVD2-Pad38)") (class "Default")
      (node (ref "U3") (pin "38") (pinfunction "RSVD2_38") (pintype "input"))
    )
    (net (code "142") (name "unconnected-(U3-RSVD3-Pad39)") (class "Default")
      (node (ref "U3") (pin "39") (pinfunction "RSVD3_39") (pintype "input"))
    )
    (net (code "143") (name "unconnected-(U3-RSVD4-Pad40)") (class "Default")
      (node (ref "U3") (pin "40") (pinfunction "RSVD4_40") (pintype "input"))
    )
    (net (code "144") (name "unconnected-(U3-RSVD5-Pad41)") (class "Default")
      (node (ref "U3") (pin "41") (pinfunction "RSVD5_41") (pintype "input"))
    )
    (net (code "145") (name "unconnected-(U3-RSVD6-Pad42)") (class "Default")
      (node (ref "U3") (pin "42") (pinfunction "RSVD6_42") (pintype "input"))
    )
    (net (code "146") (name "unconnected-(U3-SCLK-Pad33)") (class "Default")
      (node (ref "U3") (pin "33") (pinfunction "SCLK_33") (pintype "input"))
    )
    (net (code "147") (name "unconnected-(U3-SPD-Pad24)") (class "Default")
      (node (ref "U3") (pin "24") (pinfunction "SPD_24") (pintype "output"))
    )
    (net (code "148") (name "unconnected-(U3-TXN-Pad1)") (class "Default")
      (node (ref "U3") (pin "1") (pinfunction "TXN_1") (pintype "output"))
    )
    (net (code "149") (name "unconnected-(U3-TXP-Pad2)") (class "Default")
      (node (ref "U3") (pin "2") (pinfunction "TXP_2") (pintype "output"))
    )
    (net (code "150") (name "unconnected-(U3-VBG-Pad18)") (class "Default")
      (node (ref "U3") (pin "18") (pinfunction "VBG_18") (pintype "output"))
    )
    (net (code "151") (name "unconnected-(U3-~{INT}-Pad36)") (class "Default")
      (node (ref "U3") (pin "36") (pinfunction "~{INT}_36") (pintype "input"))
    )
    (net (code "152") (name "unconnected-(U3-~{RST}-Pad37)") (class "Default")
      (node (ref "U3") (pin "37") (pinfunction "~{RST}_37") (pintype "input"))
    )
    (net (code "153") (name "unconnected-(U3-~{SCS}-Pad32)") (class "Default")
      (node (ref "U3") (pin "32") (pinfunction "~{SCS}_32") (pintype "input"))
    )
    (net (code "154") (name "unconnected-(U4-GND-Pad5)") (class "Default")
      (node (ref "U4") (pin "5") (pinfunction "GND_5") (pintype "passive"))
    )
    (net (code "155") (name "unconnected-(U4-GND-Pad12)") (class "Default")
      (node (ref "U4") (pin "12") (pinfunction "GND_12") (pintype "passive"))
    )
    (net (code "156") (name "unconnected-(U4-GND-Pad13)") (class "Default")
      (node (ref "U4") (pin "13") (pinfunction "GND_13") (pintype "passive"))
    )
    (net (code "157") (name "unconnected-(U4-GND-Pad16)") (class "Default")
      (node (ref "U4") (pin "16") (pinfunction "GND_16") (pintype "passive"))
    )
    (net (code "158") (name "unconnected-(U4-INT1-Pad11)") (class "Default")
      (node (ref "U4") (pin "11") (pinfunction "INT1_11") (pintype "input"))
    )
    (net (code "159") (name "unconnected-(U4-INT2-Pad9)") (class "Default")
      (node (ref "U4") (pin "9") (pinfunction "INT2_9") (pintype "input"))
    )
    (net (code "160") (name "unconnected-(U4-NC-Pad3)") (class "Default")
      (node (ref "U4") (pin "3") (pinfunction "NC_3") (pintype "input"))
    )
    (net (code "161") (name "unconnected-(U4-NC_2-Pad2)") (class "Default")
      (node (ref "U4") (pin "2") (pinfunction "NC_2_2") (pintype "input"))
    )
    (net (code "162") (name "unconnected-(U4-SCL-Pad4)") (class "Default")
      (node (ref "U4") (pin "4") (pinfunction "SCL_4") (pintype "input"))
    )
    (net (code "163") (name "unconnected-(U4-SDA-Pad6)") (class "Default")
      (node (ref "U4") (pin "6") (pinfunction "SDA_6") (pintype "bidirectional"))
    )
    (net (code "164") (name "unconnected-(VT1A-A1-Pad1)") (class "Default")
      (node (ref "VT1") (pin "1") (pinfunction "A1_1") (pintype "passive"))
    )
    (net (code "165") (name "unconnected-(VT1A-C1-Pad8)") (class "Default")
      (node (ref "VT1") (pin "8") (pinfunction "C1_8") (pintype "passive"))
    )
    (net (code "166") (name "unconnected-(X2-+3,3V-Pad1)") (class "Default")
      (node (ref "X2") (pin "1") (pinfunction "+3,3V_1") (pintype "passive"))
    )
    (net (code "167") (name "unconnected-(X2-GND-Pad6)") (class "Default")
      (node (ref "X2") (pin "6") (pinfunction "GND_6") (pintype "passive"))
    )
    (net (code "168") (name "unconnected-(X2-N-Pad4)") (class "Default")
      (node (ref "X2") (pin "4") (pinfunction "N_4") (pintype "passive"))
    )
    (net (code "169") (name "unconnected-(X2-SWCLK-Pad2)") (class "Default")
      (node (ref "X2") (pin "2") (pinfunction "SWCLK_2") (pintype "passive"))
    )
    (net (code "170") (name "unconnected-(X2-SWDIO-Pad3)") (class "Default")
      (node (ref "X2") (pin "3") (pinfunction "SWDIO_3") (pintype "passive"))
    )
    (net (code "171") (name "unconnected-(X2-SWO-Pad5)") (class "Default")
      (node (ref "X2") (pin "5") (pinfunction "SWO_5") (pintype "passive"))
    )
  )
)
